# CAN.net
KiCad netlist of a schematic drawn in EAGLE
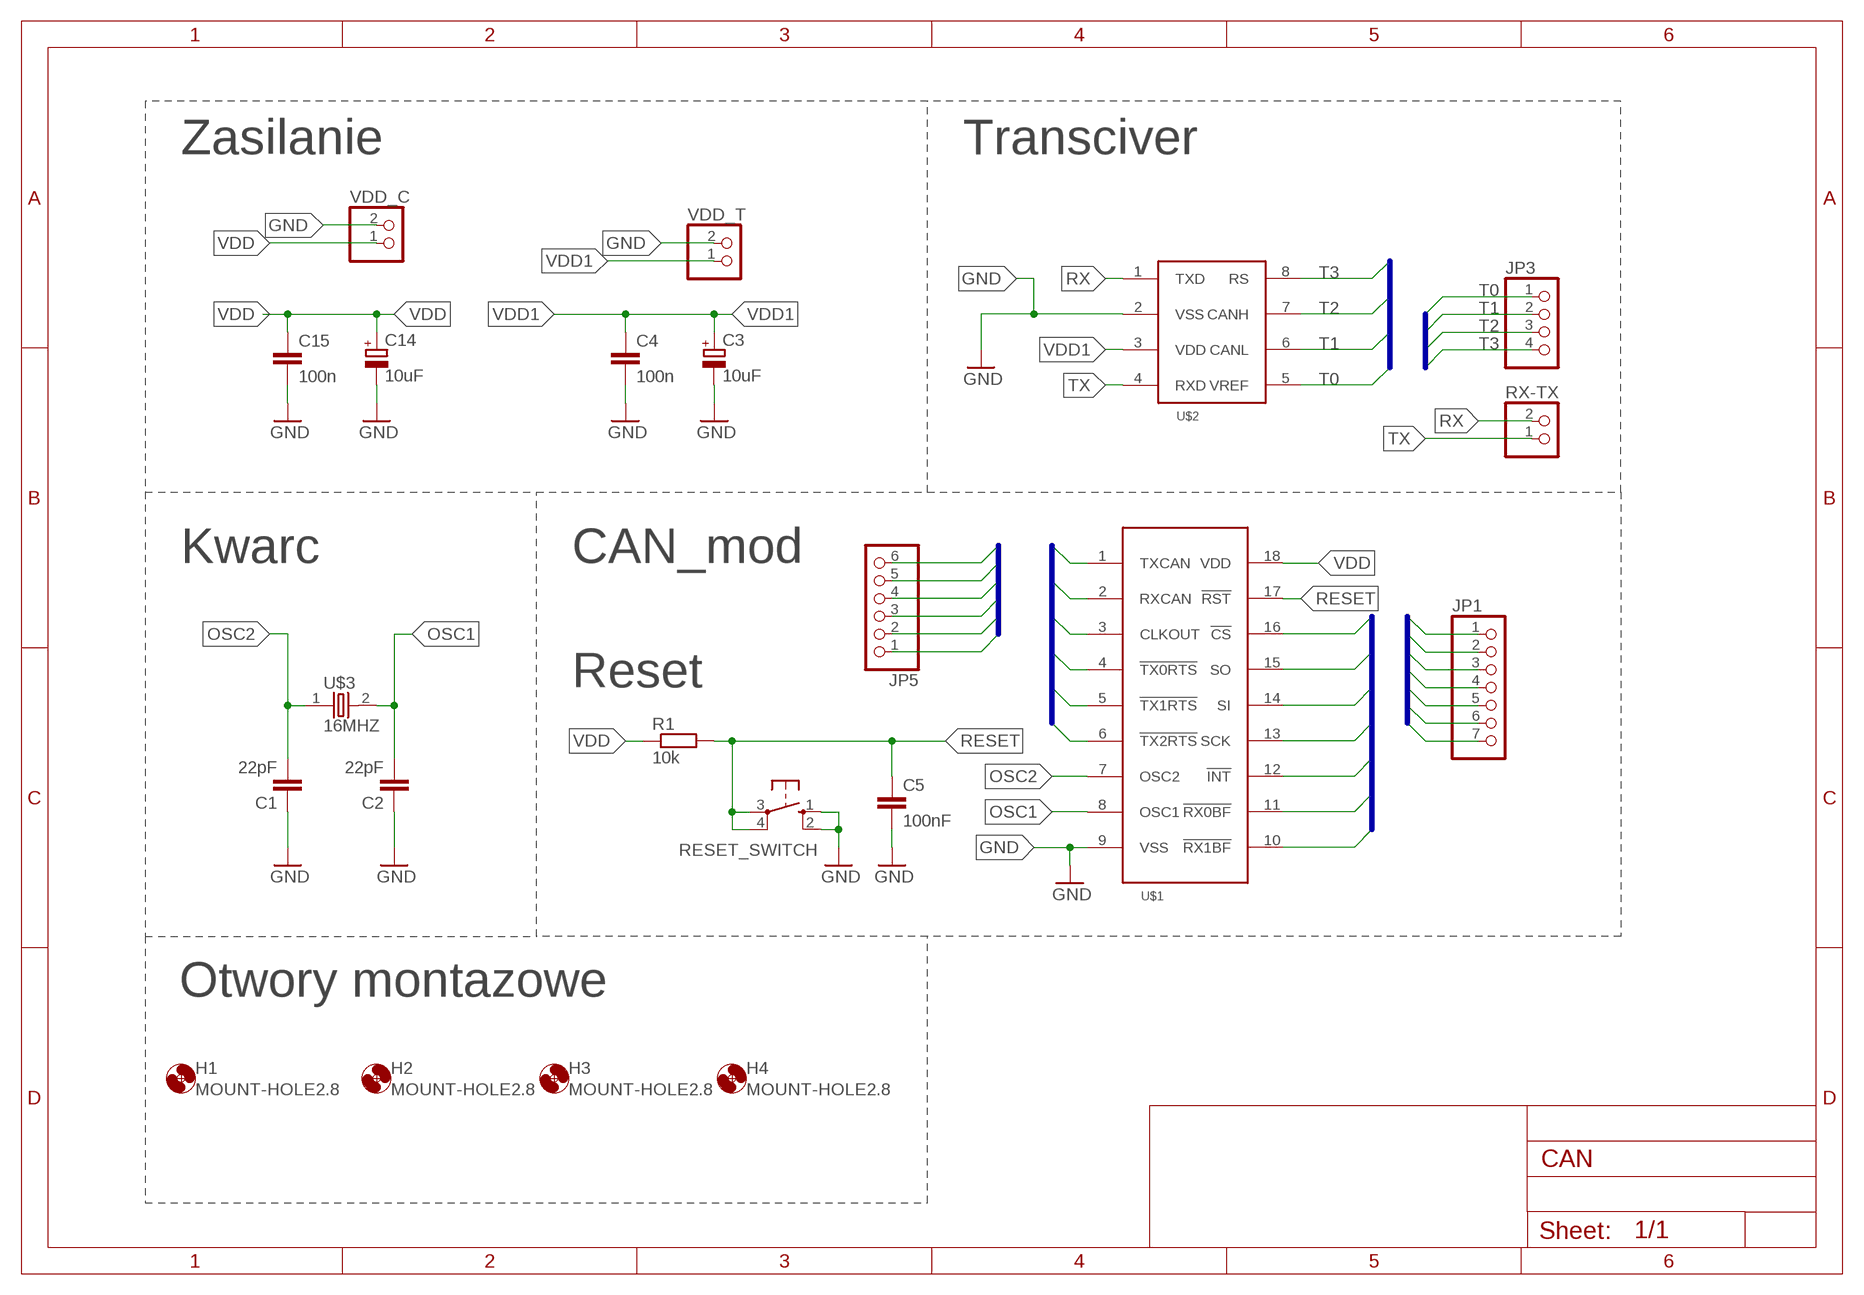
[diagram p0: schematic, sheet 1]

(export (version "E")
  (design (tool "Eeschema 10.0.6"))
  (components
    (comp (ref "C1")
      (value "22pF")
      (footprint "eagle-import:C3216")
      (libsource (lib "eagle-import") (part "C-EUC3216"))
    )
    (comp (ref "C2")
      (value "22pF")
      (footprint "eagle-import:C3216")
      (libsource (lib "eagle-import") (part "C-EUC3216"))
    )
    (comp (ref "C3")
      (value "10uF")
      (footprint "eagle-import:A_3216-18W")
      (libsource (lib "eagle-import") (part "CPOL-EUA/3216-18W"))
    )
    (comp (ref "C4")
      (value "100n")
      (footprint "eagle-import:C1206K")
      (libsource (lib "eagle-import") (part "C-EUC1206K"))
    )
    (comp (ref "C5")
      (value "100nF")
      (footprint "eagle-import:C1206K")
      (libsource (lib "eagle-import") (part "C-EUC1206K"))
    )
    (comp (ref "C14")
      (value "10uF")
      (footprint "eagle-import:A_3216-18W")
      (libsource (lib "eagle-import") (part "CPOL-EUA/3216-18W"))
    )
    (comp (ref "C15")
      (value "100n")
      (footprint "eagle-import:C1206K")
      (libsource (lib "eagle-import") (part "C-EUC1206K"))
    )
    (comp (ref "H1")
      (value "MOUNT-HOLE2.8")
      (footprint "eagle-import:2,8")
      (libsource (lib "eagle-import") (part "MOUNT-HOLE2.8"))
    )
    (comp (ref "H2")
      (value "MOUNT-HOLE2.8")
      (footprint "eagle-import:2,8")
      (libsource (lib "eagle-import") (part "MOUNT-HOLE2.8"))
    )
    (comp (ref "H3")
      (value "MOUNT-HOLE2.8")
      (footprint "eagle-import:2,8")
      (libsource (lib "eagle-import") (part "MOUNT-HOLE2.8"))
    )
    (comp (ref "H4")
      (value "MOUNT-HOLE2.8")
      (footprint "eagle-import:2,8")
      (libsource (lib "eagle-import") (part "MOUNT-HOLE2.8"))
    )
    (comp (ref "JP1")
      (value "PINHD-1X7MAT_LCD")
      (footprint "eagle-import:1X07")
      (libsource (lib "eagle-import") (part "PINHD-1X7MAT_LCD"))
    )
    (comp (ref "JP3")
      (value "PINHD-1X4")
      (footprint "eagle-import:1X04")
      (libsource (lib "eagle-import") (part "PINHD-1X4"))
    )
    (comp (ref "JP5")
      (value "PINHD-1X6MAT6")
      (footprint "eagle-import:1X06")
      (libsource (lib "eagle-import") (part "PINHD-1X6MAT6"))
    )
    (comp (ref "R1")
      (value "10k")
      (footprint "eagle-import:R3216")
      (libsource (lib "eagle-import") (part "R-EU_R3216"))
    )
    (comp (ref "RESET_SWITCH")
      (value "10-XX")
      (footprint "eagle-import:B3F-10XX")
      (fields (field (name "MPN") "B3F-1000"))
      (libsource (lib "eagle-import") (part "10-XX"))
    )
    (comp (ref "RX-TX")
      (value "PINHD-1X2")
      (footprint "eagle-import:1X02")
      (libsource (lib "eagle-import") (part "PINHD-1X2"))
    )
    (comp (ref "U$1")
      (value "MCP2515")
      (footprint "eagle-import:MCP2515")
      (libsource (lib "eagle-import") (part "MCP2515"))
    )
    (comp (ref "U$2")
      (value "MCP2551")
      (footprint "eagle-import:MCP2551")
      (libsource (lib "eagle-import") (part "MCP2551"))
    )
    (comp (ref "U$3")
      (value "16MHZ")
      (footprint "eagle-import:HC49SM")
      (libsource (lib "eagle-import") (part "16MHZ"))
    )
    (comp (ref "VDD_C")
      (value "PINHD-1X2")
      (footprint "eagle-import:1X02")
      (libsource (lib "eagle-import") (part "PINHD-1X2"))
    )
    (comp (ref "VDD_T")
      (value "PINHD-1X2")
      (footprint "eagle-import:1X02")
      (libsource (lib "eagle-import") (part "PINHD-1X2"))
    )
  )
  (nets
    (net (code "1") (name "/CAN0") (class "Default")
      (node (ref "JP1") (pin "1") (pinfunction "1_1") (pintype "passive"))
      (node (ref "U$1") (pin "10") (pinfunction "~{RX1BF}_10") (pintype "bidirectional"))
    )
    (net (code "2") (name "/CAN1") (class "Default")
      (node (ref "JP1") (pin "2") (pinfunction "2_2") (pintype "passive"))
      (node (ref "U$1") (pin "11") (pinfunction "~{RX0BF}_11") (pintype "bidirectional"))
    )
    (net (code "3") (name "/CAN2") (class "Default")
      (node (ref "JP1") (pin "3") (pinfunction "3_3") (pintype "passive"))
      (node (ref "U$1") (pin "12") (pinfunction "~{INT}_12") (pintype "bidirectional"))
    )
    (net (code "4") (name "/CAN3") (class "Default")
      (node (ref "JP1") (pin "4") (pinfunction "4_4") (pintype "passive"))
      (node (ref "U$1") (pin "13") (pinfunction "SCK_13") (pintype "bidirectional"))
    )
    (net (code "5") (name "/CAN4") (class "Default")
      (node (ref "JP1") (pin "5") (pinfunction "5_5") (pintype "passive"))
      (node (ref "U$1") (pin "14") (pinfunction "SI_14") (pintype "bidirectional"))
    )
    (net (code "6") (name "/CAN5") (class "Default")
      (node (ref "JP1") (pin "6") (pinfunction "6_6") (pintype "passive"))
      (node (ref "U$1") (pin "15") (pinfunction "SO_15") (pintype "bidirectional"))
    )
    (net (code "7") (name "/CAN6") (class "Default")
      (node (ref "JP1") (pin "7") (pinfunction "7_7") (pintype "passive"))
      (node (ref "U$1") (pin "16") (pinfunction "~{CS}_16") (pintype "bidirectional"))
    )
    (net (code "8") (name "/CANL0") (class "Default")
      (node (ref "JP5") (pin "1") (pinfunction "1_1") (pintype "passive"))
      (node (ref "U$1") (pin "6") (pinfunction "~{TX2RTS}_6") (pintype "bidirectional"))
    )
    (net (code "9") (name "/CANL1") (class "Default")
      (node (ref "JP5") (pin "2") (pinfunction "2_2") (pintype "passive"))
      (node (ref "U$1") (pin "5") (pinfunction "~{TX1RTS}_5") (pintype "bidirectional"))
    )
    (net (code "10") (name "/CANL2") (class "Default")
      (node (ref "JP5") (pin "3") (pinfunction "3_3") (pintype "passive"))
      (node (ref "U$1") (pin "4") (pinfunction "~{TX0RTS}_4") (pintype "bidirectional"))
    )
    (net (code "11") (name "/CANL3") (class "Default")
      (node (ref "JP5") (pin "4") (pinfunction "4_4") (pintype "passive"))
      (node (ref "U$1") (pin "3") (pinfunction "CLKOUT_3") (pintype "bidirectional"))
    )
    (net (code "12") (name "/CANL4") (class "Default")
      (node (ref "JP5") (pin "5") (pinfunction "5_5") (pintype "passive"))
      (node (ref "U$1") (pin "2") (pinfunction "RXCAN_2") (pintype "bidirectional"))
    )
    (net (code "13") (name "/CANL5") (class "Default")
      (node (ref "JP5") (pin "6") (pinfunction "6_6") (pintype "passive"))
      (node (ref "U$1") (pin "1") (pinfunction "TXCAN_1") (pintype "bidirectional"))
    )
    (net (code "14") (name "/T0") (class "Default")
      (node (ref "JP3") (pin "1") (pinfunction "1_1") (pintype "passive"))
      (node (ref "U$2") (pin "5") (pinfunction "VREF_5") (pintype "bidirectional"))
    )
    (net (code "15") (name "/T1") (class "Default")
      (node (ref "JP3") (pin "2") (pinfunction "2_2") (pintype "passive"))
      (node (ref "U$2") (pin "6") (pinfunction "CANL_6") (pintype "bidirectional"))
    )
    (net (code "16") (name "/T2") (class "Default")
      (node (ref "JP3") (pin "3") (pinfunction "3_3") (pintype "passive"))
      (node (ref "U$2") (pin "7") (pinfunction "CANH_7") (pintype "bidirectional"))
    )
    (net (code "17") (name "/T3") (class "Default")
      (node (ref "JP3") (pin "4") (pinfunction "4_4") (pintype "passive"))
      (node (ref "U$2") (pin "8") (pinfunction "RS_8") (pintype "bidirectional"))
    )
    (net (code "18") (name "GND") (class "Default")
      (node (ref "C1") (pin "1") (pinfunction "1_1") (pintype "passive"))
      (node (ref "C14") (pin "-") (pinfunction "-_-") (pintype "passive"))
      (node (ref "C15") (pin "2") (pinfunction "2_2") (pintype "passive"))
      (node (ref "C2") (pin "1") (pinfunction "1_1") (pintype "passive"))
      (node (ref "C3") (pin "-") (pinfunction "-_-") (pintype "passive"))
      (node (ref "C4") (pin "2") (pinfunction "2_2") (pintype "passive"))
      (node (ref "C5") (pin "2") (pinfunction "2_2") (pintype "passive"))
      (node (ref "RESET_SWITCH") (pin "1") (pinfunction "S_1") (pintype "passive"))
      (node (ref "RESET_SWITCH") (pin "2") (pinfunction "S1_2") (pintype "passive"))
      (node (ref "U$1") (pin "9") (pinfunction "VSS_9") (pintype "bidirectional"))
      (node (ref "U$2") (pin "2") (pinfunction "VSS_2") (pintype "bidirectional"))
      (node (ref "VDD_C") (pin "2") (pinfunction "1_2") (pintype "passive"))
      (node (ref "VDD_T") (pin "2") (pinfunction "1_2") (pintype "passive"))
    )
    (net (code "19") (name "OSC1") (class "Default")
      (node (ref "C2") (pin "2") (pinfunction "2_2") (pintype "passive"))
      (node (ref "U$1") (pin "8") (pinfunction "OSC1_8") (pintype "bidirectional"))
      (node (ref "U$3") (pin "2") (pinfunction "2_2") (pintype "passive"))
    )
    (net (code "20") (name "OSC2") (class "Default")
      (node (ref "C1") (pin "2") (pinfunction "2_2") (pintype "passive"))
      (node (ref "U$1") (pin "7") (pinfunction "OSC2_7") (pintype "bidirectional"))
      (node (ref "U$3") (pin "1") (pinfunction "1_1") (pintype "passive"))
    )
    (net (code "21") (name "RESET") (class "Default")
      (node (ref "C5") (pin "1") (pinfunction "1_1") (pintype "passive"))
      (node (ref "R1") (pin "2") (pinfunction "2_2") (pintype "passive"))
      (node (ref "RESET_SWITCH") (pin "3") (pinfunction "P_3") (pintype "passive"))
      (node (ref "RESET_SWITCH") (pin "4") (pinfunction "P1_4") (pintype "passive"))
      (node (ref "U$1") (pin "17") (pinfunction "~{RST}_17") (pintype "bidirectional"))
    )
    (net (code "22") (name "RX") (class "Default")
      (node (ref "RX-TX") (pin "2") (pinfunction "1_2") (pintype "passive"))
      (node (ref "U$2") (pin "1") (pinfunction "TXD_1") (pintype "bidirectional"))
    )
    (net (code "23") (name "TX") (class "Default")
      (node (ref "RX-TX") (pin "1") (pinfunction "2_1") (pintype "passive"))
      (node (ref "U$2") (pin "4") (pinfunction "RXD_4") (pintype "bidirectional"))
    )
    (net (code "24") (name "VDD") (class "Default")
      (node (ref "C14") (pin "+") (pinfunction "+_+") (pintype "passive"))
      (node (ref "C15") (pin "1") (pinfunction "1_1") (pintype "passive"))
      (node (ref "R1") (pin "1") (pinfunction "1_1") (pintype "passive"))
      (node (ref "U$1") (pin "18") (pinfunction "VDD_18") (pintype "bidirectional"))
      (node (ref "VDD_C") (pin "1") (pinfunction "2_1") (pintype "passive"))
    )
    (net (code "25") (name "VDD1") (class "Default")
      (node (ref "C3") (pin "+") (pinfunction "+_+") (pintype "passive"))
      (node (ref "C4") (pin "1") (pinfunction "1_1") (pintype "passive"))
      (node (ref "U$2") (pin "3") (pinfunction "VDD_3") (pintype "bidirectional"))
      (node (ref "VDD_T") (pin "1") (pinfunction "2_1") (pintype "passive"))
    )
  )
)
